# Triggy_0_3.net
KiCad netlist of a schematic drawn in EAGLE
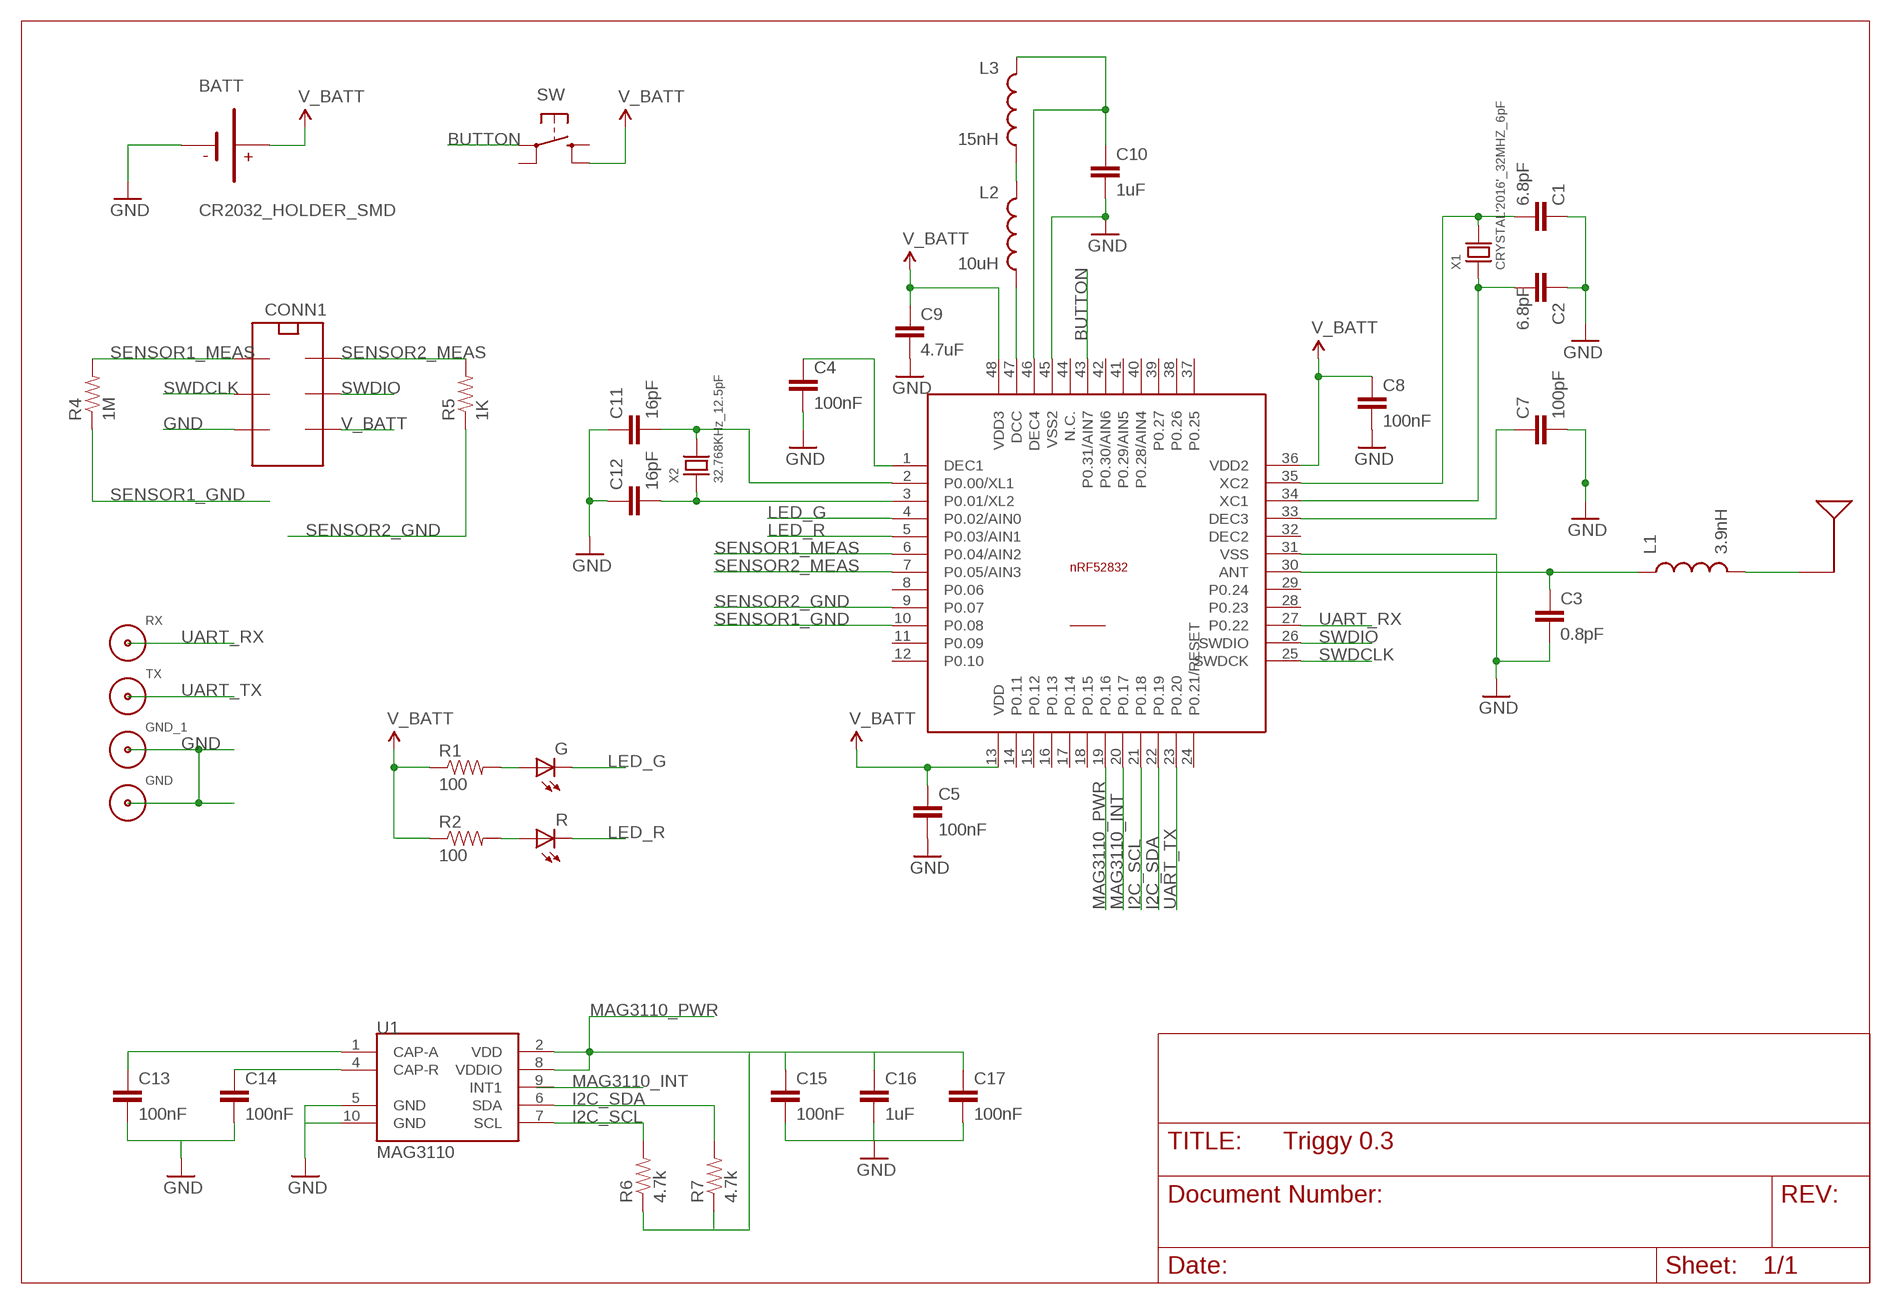
[diagram p0: schematic, sheet 1]

(export (version "E")
  (design (tool "Eeschema 10.0.6"))
  (components
    (comp (ref "ANT")
      (value "ANTENNA_2450AT43A100")
      (footprint "eagle-import:ANTENNA-SMD-7MM")
      (libsource (lib "eagle-import") (part "ANTENNA_2450AT43A100"))
    )
    (comp (ref "BATT")
      (value "CR2032_HOLDER_SMD")
      (footprint "eagle-import:CR2032_HOLDER_SMD")
      (libsource (lib "eagle-import") (part "CR2032_HOLDER_SMD"))
    )
    (comp (ref "C1")
      (value "6.8pF")
      (footprint "eagle-import:0402-CAP")
      (libsource (lib "eagle-import") (part "CAP0402-CAP"))
    )
    (comp (ref "C2")
      (value "6.8pF")
      (footprint "eagle-import:0402-CAP")
      (libsource (lib "eagle-import") (part "CAP0402-CAP"))
    )
    (comp (ref "C3")
      (value "0.8pF")
      (footprint "eagle-import:0402-CAP")
      (libsource (lib "eagle-import") (part "CAP0402-CAP"))
    )
    (comp (ref "C4")
      (value "100nF")
      (footprint "eagle-import:0402-CAP")
      (libsource (lib "eagle-import") (part "CAP0402-CAP"))
    )
    (comp (ref "C5")
      (value "100nF")
      (footprint "eagle-import:0402-CAP")
      (libsource (lib "eagle-import") (part "CAP0402-CAP"))
    )
    (comp (ref "C7")
      (value "100pF")
      (footprint "eagle-import:0402-CAP")
      (libsource (lib "eagle-import") (part "CAP0402-CAP"))
    )
    (comp (ref "C8")
      (value "100nF")
      (footprint "eagle-import:0402-CAP")
      (libsource (lib "eagle-import") (part "CAP0402-CAP"))
    )
    (comp (ref "C9")
      (value "4.7uF")
      (footprint "eagle-import:0603-CAP")
      (libsource (lib "eagle-import") (part "CAP0603-CAP"))
    )
    (comp (ref "C10")
      (value "1uF")
      (footprint "eagle-import:0603-CAP")
      (libsource (lib "eagle-import") (part "CAP0603-CAP"))
    )
    (comp (ref "C11")
      (value "16pF")
      (footprint "eagle-import:0402-CAP")
      (libsource (lib "eagle-import") (part "CAP0402-CAP"))
    )
    (comp (ref "C12")
      (value "16pF")
      (footprint "eagle-import:0402-CAP")
      (libsource (lib "eagle-import") (part "CAP0402-CAP"))
    )
    (comp (ref "C13")
      (value "100nF")
      (footprint "eagle-import:0402-CAP")
      (libsource (lib "eagle-import") (part "CAP0402-CAP"))
    )
    (comp (ref "C14")
      (value "100nF")
      (footprint "eagle-import:0402-CAP")
      (libsource (lib "eagle-import") (part "CAP0402-CAP"))
    )
    (comp (ref "C15")
      (value "100nF")
      (footprint "eagle-import:0402-CAP")
      (libsource (lib "eagle-import") (part "CAP0402-CAP"))
    )
    (comp (ref "C16")
      (value "1uF")
      (footprint "eagle-import:0603-CAP")
      (libsource (lib "eagle-import") (part "CAP0603-CAP"))
    )
    (comp (ref "C17")
      (value "100nF")
      (footprint "eagle-import:0402-CAP")
      (libsource (lib "eagle-import") (part "CAP0402-CAP"))
    )
    (comp (ref "CONN1")
      (value "MOLEX_8734006XX")
      (footprint "eagle-import:MOLEX_8734006XX")
      (libsource (lib "eagle-import") (part "MOLEX_8734006XX"))
    )
    (comp (ref "GND")
      (value "SINGLE_CONN")
      (footprint "eagle-import:SINGLE-CONN")
      (libsource (lib "eagle-import") (part "SINGLE_CONN"))
    )
    (comp (ref "GND_1")
      (value "SINGLE_CONN")
      (footprint "eagle-import:SINGLE-CONN")
      (libsource (lib "eagle-import") (part "SINGLE_CONN"))
    )
    (comp (ref "L1")
      (value "3.9nH")
      (footprint "eagle-import:C0402")
      (libsource (lib "eagle-import") (part "INDUCTOR0402"))
    )
    (comp (ref "L2")
      (value "10uH")
      (footprint "eagle-import:0603")
      (libsource (lib "eagle-import") (part "INDUCTOR0603"))
    )
    (comp (ref "L3")
      (value "15nH")
      (footprint "eagle-import:C0402")
      (libsource (lib "eagle-import") (part "INDUCTOR0402"))
    )
    (comp (ref "LEDS")
      (value "LED-R-G")
      (footprint "eagle-import:LED-RG-SMD-3X2.5MM")
      (libsource (lib "eagle-import") (part "LED-R-G"))
    )
    (comp (ref "NRF52832")
      (value "NRF52832_QFN")
      (footprint "eagle-import:QFN48")
      (libsource (lib "eagle-import") (part "NRF52832_QFN"))
    )
    (comp (ref "R1")
      (value "100")
      (footprint "eagle-import:0402-RES")
      (libsource (lib "eagle-import") (part "RESISTOR0402"))
    )
    (comp (ref "R2")
      (value "100")
      (footprint "eagle-import:0402-RES")
      (libsource (lib "eagle-import") (part "RESISTOR0402"))
    )
    (comp (ref "R4")
      (value "1M")
      (footprint "eagle-import:0402-RES")
      (libsource (lib "eagle-import") (part "RESISTOR0402"))
    )
    (comp (ref "R5")
      (value "1K")
      (footprint "eagle-import:0402-RES")
      (libsource (lib "eagle-import") (part "RESISTOR0402"))
    )
    (comp (ref "R6")
      (value "4.7k")
      (footprint "eagle-import:0402-RES")
      (libsource (lib "eagle-import") (part "RESISTOR0402"))
    )
    (comp (ref "R7")
      (value "4.7k")
      (footprint "eagle-import:0402-RES")
      (libsource (lib "eagle-import") (part "RESISTOR0402"))
    )
    (comp (ref "RX")
      (value "SINGLE_CONN")
      (footprint "eagle-import:SINGLE-CONN")
      (libsource (lib "eagle-import") (part "SINGLE_CONN"))
    )
    (comp (ref "SW")
      (value "SWITCH-PANASONIC")
      (footprint "eagle-import:SWITCH-PANASONIC")
      (libsource (lib "eagle-import") (part "SWITCH-PANASONIC"))
    )
    (comp (ref "TX")
      (value "SINGLE_CONN")
      (footprint "eagle-import:SINGLE-CONN")
      (libsource (lib "eagle-import") (part "SINGLE_CONN"))
    )
    (comp (ref "U1")
      (value "MAG3110")
      (footprint "eagle-import:DFN-10")
      (libsource (lib "eagle-import") (part "MAG3110"))
    )
    (comp (ref "X1")
      (value "CRYSTAL'2016'_32MHZ_6pF")
      (footprint "eagle-import:X4-SMD-2.0X1.6MM")
      (libsource (lib "eagle-import") (part "CRYSTAL'2016'_32MHZ"))
    )
    (comp (ref "X2")
      (value "32.768KHz_12.5pF")
      (footprint "eagle-import:X2-SMD-3.2X1.5MM")
      (libsource (lib "eagle-import") (part "CRYSTAL'3215'"))
    )
  )
  (nets
    (net (code "1") (name "/BUTTON") (class "Default")
      (node (ref "NRF52832") (pin "43") (pinfunction "P0.31/AIN7_43") (pintype "bidirectional"))
      (node (ref "SW") (pin "A") (pinfunction "1_A") (pintype "passive"))
    )
    (net (code "2") (name "/DEC2") (class "Default")
      (node (ref "NRF52832") (pin "32") (pinfunction "DEC2_32") (pintype "power_in"))
    )
    (net (code "3") (name "/I2C_SCL") (class "Default")
      (node (ref "NRF52832") (pin "21") (pinfunction "P0.18_21") (pintype "bidirectional"))
      (node (ref "R6") (pin "2") (pinfunction "2_2") (pintype "passive"))
      (node (ref "U1") (pin "7") (pinfunction "SCL_7") (pintype "bidirectional"))
    )
    (net (code "4") (name "/I2C_SDA") (class "Default")
      (node (ref "NRF52832") (pin "22") (pinfunction "P0.19_22") (pintype "bidirectional"))
      (node (ref "R7") (pin "2") (pinfunction "2_2") (pintype "passive"))
      (node (ref "U1") (pin "6") (pinfunction "SDA_6") (pintype "bidirectional"))
    )
    (net (code "5") (name "/LED_G") (class "Default")
      (node (ref "LEDS") (pin "P$4") (pinfunction "P4_P$4") (pintype "passive"))
      (node (ref "NRF52832") (pin "4") (pinfunction "P0.02/AIN0_4") (pintype "bidirectional"))
    )
    (net (code "6") (name "/LED_R") (class "Default")
      (node (ref "LEDS") (pin "P$2") (pinfunction "P2_P$2") (pintype "passive"))
      (node (ref "NRF52832") (pin "5") (pinfunction "P0.03/AIN1_5") (pintype "bidirectional"))
    )
    (net (code "7") (name "/MAG3110_INT") (class "Default")
      (node (ref "NRF52832") (pin "20") (pinfunction "P0.17_20") (pintype "bidirectional"))
      (node (ref "U1") (pin "9") (pinfunction "INT1_9") (pintype "bidirectional"))
    )
    (net (code "8") (name "/MAG3110_PWR") (class "Default")
      (node (ref "C15") (pin "1") (pinfunction "1_1") (pintype "passive"))
      (node (ref "C16") (pin "1") (pinfunction "1_1") (pintype "passive"))
      (node (ref "C17") (pin "1") (pinfunction "1_1") (pintype "passive"))
      (node (ref "NRF52832") (pin "19") (pinfunction "P0.16_19") (pintype "bidirectional"))
      (node (ref "R6") (pin "1") (pinfunction "1_1") (pintype "passive"))
      (node (ref "R7") (pin "1") (pinfunction "1_1") (pintype "passive"))
      (node (ref "U1") (pin "2") (pinfunction "VDD_2") (pintype "bidirectional"))
      (node (ref "U1") (pin "8") (pinfunction "VDDIO_8") (pintype "bidirectional"))
    )
    (net (code "9") (name "/SENSOR1_GND") (class "Default")
      (node (ref "NRF52832") (pin "10") (pinfunction "P0.08_10") (pintype "bidirectional"))
      (node (ref "R4") (pin "1") (pinfunction "1_1") (pintype "passive"))
    )
    (net (code "10") (name "/SENSOR1_MEAS") (class "Default")
      (node (ref "CONN1") (pin "P$1") (pinfunction "P$1_P$1") (pintype "bidirectional"))
      (node (ref "NRF52832") (pin "6") (pinfunction "P0.04/AIN2_6") (pintype "bidirectional"))
      (node (ref "R4") (pin "2") (pinfunction "2_2") (pintype "passive"))
    )
    (net (code "11") (name "/SENSOR2_GND") (class "Default")
      (node (ref "NRF52832") (pin "9") (pinfunction "P0.07_9") (pintype "bidirectional"))
      (node (ref "R5") (pin "1") (pinfunction "1_1") (pintype "passive"))
    )
    (net (code "12") (name "/SENSOR2_MEAS") (class "Default")
      (node (ref "CONN1") (pin "P$2") (pinfunction "P$2_P$2") (pintype "bidirectional"))
      (node (ref "NRF52832") (pin "7") (pinfunction "P0.05/AIN3_7") (pintype "bidirectional"))
      (node (ref "R5") (pin "2") (pinfunction "2_2") (pintype "passive"))
    )
    (net (code "13") (name "/SWDCLK") (class "Default")
      (node (ref "CONN1") (pin "P$3") (pinfunction "P$3_P$3") (pintype "bidirectional"))
      (node (ref "NRF52832") (pin "25") (pinfunction "SWDCK_25") (pintype "open_collector"))
    )
    (net (code "14") (name "/SWDIO") (class "Default")
      (node (ref "CONN1") (pin "P$4") (pinfunction "P$4_P$4") (pintype "bidirectional"))
      (node (ref "NRF52832") (pin "26") (pinfunction "SWDIO_26") (pintype "bidirectional"))
    )
    (net (code "15") (name "/UART_RX") (class "Default")
      (node (ref "NRF52832") (pin "27") (pinfunction "P0.22_27") (pintype "bidirectional"))
      (node (ref "RX") (pin "1") (pinfunction "1_1") (pintype "bidirectional"))
    )
    (net (code "16") (name "/UART_TX") (class "Default")
      (node (ref "NRF52832") (pin "23") (pinfunction "P0.20_23") (pintype "bidirectional"))
      (node (ref "TX") (pin "1") (pinfunction "1_1") (pintype "bidirectional"))
    )
    (net (code "17") (name "GND") (class "Default")
      (node (ref "BATT") (pin "-") (pinfunction "-_-") (pintype "power_in"))
      (node (ref "C1") (pin "1") (pinfunction "1_1") (pintype "passive"))
      (node (ref "C10") (pin "2") (pinfunction "2_2") (pintype "passive"))
      (node (ref "C11") (pin "1") (pinfunction "1_1") (pintype "passive"))
      (node (ref "C12") (pin "1") (pinfunction "1_1") (pintype "passive"))
      (node (ref "C13") (pin "2") (pinfunction "2_2") (pintype "passive"))
      (node (ref "C14") (pin "2") (pinfunction "2_2") (pintype "passive"))
      (node (ref "C15") (pin "2") (pinfunction "2_2") (pintype "passive"))
      (node (ref "C16") (pin "2") (pinfunction "2_2") (pintype "passive"))
      (node (ref "C17") (pin "2") (pinfunction "2_2") (pintype "passive"))
      (node (ref "C2") (pin "1") (pinfunction "1_1") (pintype "passive"))
      (node (ref "C3") (pin "2") (pinfunction "2_2") (pintype "passive"))
      (node (ref "C4") (pin "2") (pinfunction "2_2") (pintype "passive"))
      (node (ref "C5") (pin "2") (pinfunction "2_2") (pintype "passive"))
      (node (ref "C7") (pin "2") (pinfunction "2_2") (pintype "passive"))
      (node (ref "C8") (pin "2") (pinfunction "2_2") (pintype "passive"))
      (node (ref "C9") (pin "2") (pinfunction "2_2") (pintype "passive"))
      (node (ref "CONN1") (pin "P$5") (pinfunction "P$5_P$5") (pintype "bidirectional"))
      (node (ref "GND") (pin "1") (pinfunction "1_1") (pintype "bidirectional"))
      (node (ref "GND_1") (pin "1") (pinfunction "1_1") (pintype "bidirectional"))
      (node (ref "NRF52832") (pin "31") (pinfunction "VSS_31") (pintype "power_in"))
      (node (ref "NRF52832") (pin "45") (pinfunction "VSS2_45") (pintype "power_in"))
      (node (ref "U1") (pin "10") (pinfunction "GND_10") (pintype "bidirectional"))
      (node (ref "U1") (pin "5") (pinfunction "GND_5") (pintype "bidirectional"))
    )
    (net (code "18") (name "Net-(ANT-P$1)") (class "Default")
      (node (ref "ANT") (pin "1") (pinfunction "P$1_1") (pintype "bidirectional"))
      (node (ref "L1") (pin "2") (pinfunction "2_2") (pintype "passive"))
    )
    (net (code "19") (name "Net-(L2-Pad1)") (class "Default")
      (node (ref "L2") (pin "1") (pinfunction "1_1") (pintype "passive"))
      (node (ref "L3") (pin "2") (pinfunction "2_2") (pintype "passive"))
    )
    (net (code "20") (name "Net-(LEDS-P1)") (class "Default")
      (node (ref "LEDS") (pin "P$1") (pinfunction "P1_P$1") (pintype "passive"))
      (node (ref "R2") (pin "2") (pinfunction "2_2") (pintype "passive"))
    )
    (net (code "21") (name "Net-(LEDS-P3)") (class "Default")
      (node (ref "LEDS") (pin "P$3") (pinfunction "P3_P$3") (pintype "passive"))
      (node (ref "R1") (pin "2") (pinfunction "2_2") (pintype "passive"))
    )
    (net (code "22") (name "Net-(NRF52832-ANT)") (class "Default")
      (node (ref "C3") (pin "1") (pinfunction "1_1") (pintype "passive"))
      (node (ref "L1") (pin "1") (pinfunction "1_1") (pintype "passive"))
      (node (ref "NRF52832") (pin "30") (pinfunction "ANT_30") (pintype "bidirectional"))
    )
    (net (code "23") (name "Net-(NRF52832-DCC)") (class "Default")
      (node (ref "L2") (pin "2") (pinfunction "2_2") (pintype "passive"))
      (node (ref "NRF52832") (pin "47") (pinfunction "DCC_47") (pintype "power_in"))
    )
    (net (code "24") (name "Net-(NRF52832-DEC1)") (class "Default")
      (node (ref "C4") (pin "1") (pinfunction "1_1") (pintype "passive"))
      (node (ref "NRF52832") (pin "1") (pinfunction "DEC1_1") (pintype "power_in"))
    )
    (net (code "25") (name "Net-(NRF52832-DEC3)") (class "Default")
      (node (ref "C7") (pin "1") (pinfunction "1_1") (pintype "passive"))
      (node (ref "NRF52832") (pin "33") (pinfunction "DEC3_33") (pintype "power_in"))
    )
    (net (code "26") (name "Net-(NRF52832-DEC4)") (class "Default")
      (node (ref "C10") (pin "1") (pinfunction "1_1") (pintype "passive"))
      (node (ref "L3") (pin "1") (pinfunction "1_1") (pintype "passive"))
      (node (ref "NRF52832") (pin "46") (pinfunction "DEC4_46") (pintype "bidirectional"))
    )
    (net (code "27") (name "Net-(NRF52832-P0.00{slash}XL1)") (class "Default")
      (node (ref "C11") (pin "2") (pinfunction "2_2") (pintype "passive"))
      (node (ref "NRF52832") (pin "2") (pinfunction "P0.00/XL1_2") (pintype "bidirectional"))
      (node (ref "X2") (pin "P$2") (pinfunction "2_P$2") (pintype "passive"))
    )
    (net (code "28") (name "Net-(NRF52832-P0.01{slash}XL2)") (class "Default")
      (node (ref "C12") (pin "2") (pinfunction "2_2") (pintype "passive"))
      (node (ref "NRF52832") (pin "3") (pinfunction "P0.01/XL2_3") (pintype "bidirectional"))
      (node (ref "X2") (pin "P$1") (pinfunction "1_P$1") (pintype "passive"))
    )
    (net (code "29") (name "Net-(NRF52832-XC1)") (class "Default")
      (node (ref "C2") (pin "2") (pinfunction "2_2") (pintype "passive"))
      (node (ref "NRF52832") (pin "34") (pinfunction "XC1_34") (pintype "bidirectional"))
      (node (ref "X1") (pin "2") (pinfunction "1_2") (pintype "passive"))
    )
    (net (code "30") (name "Net-(NRF52832-XC2)") (class "Default")
      (node (ref "C1") (pin "2") (pinfunction "2_2") (pintype "passive"))
      (node (ref "NRF52832") (pin "35") (pinfunction "XC2_35") (pintype "bidirectional"))
      (node (ref "X1") (pin "4") (pinfunction "2_4") (pintype "passive"))
    )
    (net (code "31") (name "Net-(U1-CAP-A)") (class "Default")
      (node (ref "C13") (pin "1") (pinfunction "1_1") (pintype "passive"))
      (node (ref "U1") (pin "1") (pinfunction "CAP-A_1") (pintype "bidirectional"))
    )
    (net (code "32") (name "Net-(U1-CAP-R)") (class "Default")
      (node (ref "C14") (pin "1") (pinfunction "1_1") (pintype "passive"))
      (node (ref "U1") (pin "4") (pinfunction "CAP-R_4") (pintype "bidirectional"))
    )
    (net (code "33") (name "V_BATT") (class "Default")
      (node (ref "BATT") (pin "+") (pinfunction "+_+") (pintype "power_in"))
      (node (ref "BATT") (pin "+@") (pinfunction "+_+@") (pintype "power_in"))
      (node (ref "C5") (pin "1") (pinfunction "1_1") (pintype "passive"))
      (node (ref "C8") (pin "1") (pinfunction "1_1") (pintype "passive"))
      (node (ref "C9") (pin "1") (pinfunction "1_1") (pintype "passive"))
      (node (ref "CONN1") (pin "P$6") (pinfunction "P$6_P$6") (pintype "bidirectional"))
      (node (ref "NRF52832") (pin "13") (pinfunction "VDD_13") (pintype "power_in"))
      (node (ref "NRF52832") (pin "36") (pinfunction "VDD2_36") (pintype "power_in"))
      (node (ref "NRF52832") (pin "48") (pinfunction "VDD3_48") (pintype "power_in"))
      (node (ref "R1") (pin "1") (pinfunction "1_1") (pintype "passive"))
      (node (ref "R2") (pin "1") (pinfunction "1_1") (pintype "passive"))
      (node (ref "SW") (pin "B'") (pinfunction "4_B'") (pintype "passive"))
    )
    (net (code "34") (name "unconnected-(NRF52832-N.C.-Pad44)") (class "Default")
      (node (ref "NRF52832") (pin "44") (pinfunction "N.C._44") (pintype "no_connect"))
    )
    (net (code "35") (name "unconnected-(NRF52832-P0.06-Pad8)") (class "Default")
      (node (ref "NRF52832") (pin "8") (pinfunction "P0.06_8") (pintype "bidirectional"))
    )
    (net (code "36") (name "unconnected-(NRF52832-P0.09-Pad11)") (class "Default")
      (node (ref "NRF52832") (pin "11") (pinfunction "P0.09_11") (pintype "bidirectional"))
    )
    (net (code "37") (name "unconnected-(NRF52832-P0.10-Pad12)") (class "Default")
      (node (ref "NRF52832") (pin "12") (pinfunction "P0.10_12") (pintype "bidirectional"))
    )
    (net (code "38") (name "unconnected-(NRF52832-P0.11-Pad14)") (class "Default")
      (node (ref "NRF52832") (pin "14") (pinfunction "P0.11_14") (pintype "bidirectional"))
    )
    (net (code "39") (name "unconnected-(NRF52832-P0.12-Pad15)") (class "Default")
      (node (ref "NRF52832") (pin "15") (pinfunction "P0.12_15") (pintype "bidirectional"))
    )
    (net (code "40") (name "unconnected-(NRF52832-P0.13-Pad16)") (class "Default")
      (node (ref "NRF52832") (pin "16") (pinfunction "P0.13_16") (pintype "bidirectional"))
    )
    (net (code "41") (name "unconnected-(NRF52832-P0.14-Pad17)") (class "Default")
      (node (ref "NRF52832") (pin "17") (pinfunction "P0.14_17") (pintype "bidirectional"))
    )
    (net (code "42") (name "unconnected-(NRF52832-P0.15-Pad18)") (class "Default")
      (node (ref "NRF52832") (pin "18") (pinfunction "P0.15_18") (pintype "bidirectional"))
    )
    (net (code "43") (name "unconnected-(NRF52832-P0.21{slash}RESET-Pad24)") (class "Default")
      (node (ref "NRF52832") (pin "24") (pinfunction "P0.21/RESET_24") (pintype "bidirectional"))
    )
    (net (code "44") (name "unconnected-(NRF52832-P0.23-Pad28)") (class "Default")
      (node (ref "NRF52832") (pin "28") (pinfunction "P0.23_28") (pintype "bidirectional"))
    )
    (net (code "45") (name "unconnected-(NRF52832-P0.24-Pad29)") (class "Default")
      (node (ref "NRF52832") (pin "29") (pinfunction "P0.24_29") (pintype "bidirectional"))
    )
    (net (code "46") (name "unconnected-(NRF52832-P0.25-Pad37)") (class "Default")
      (node (ref "NRF52832") (pin "37") (pinfunction "P0.25_37") (pintype "bidirectional"))
    )
    (net (code "47") (name "unconnected-(NRF52832-P0.26-Pad38)") (class "Default")
      (node (ref "NRF52832") (pin "38") (pinfunction "P0.26_38") (pintype "bidirectional"))
    )
    (net (code "48") (name "unconnected-(NRF52832-P0.27-Pad39)") (class "Default")
      (node (ref "NRF52832") (pin "39") (pinfunction "P0.27_39") (pintype "bidirectional"))
    )
    (net (code "49") (name "unconnected-(NRF52832-P0.28{slash}AIN4-Pad40)") (class "Default")
      (node (ref "NRF52832") (pin "40") (pinfunction "P0.28/AIN4_40") (pintype "bidirectional"))
    )
    (net (code "50") (name "unconnected-(NRF52832-P0.29{slash}AIN5-Pad41)") (class "Default")
      (node (ref "NRF52832") (pin "41") (pinfunction "P0.29/AIN5_41") (pintype "bidirectional"))
    )
    (net (code "51") (name "unconnected-(NRF52832-P0.30{slash}AIN6-Pad42)") (class "Default")
      (node (ref "NRF52832") (pin "42") (pinfunction "P0.30/AIN6_42") (pintype "bidirectional"))
    )
    (net (code "52") (name "unconnected-(NRF52832-SLUG-PadGND)") (class "Default")
      (node (ref "NRF52832") (pin "GND") (pinfunction "SLUG_GND") (pintype "bidirectional"))
    )
    (net (code "53") (name "unconnected-(SW-2-PadA')") (class "Default")
      (node (ref "SW") (pin "A'") (pinfunction "2_A'") (pintype "passive"))
    )
    (net (code "54") (name "unconnected-(SW-3-PadB)") (class "Default")
      (node (ref "SW") (pin "B") (pinfunction "3_B") (pintype "passive"))
    )
  )
)
